# esquemacamiseta2.net
KiCad netlist of a schematic drawn in EAGLE
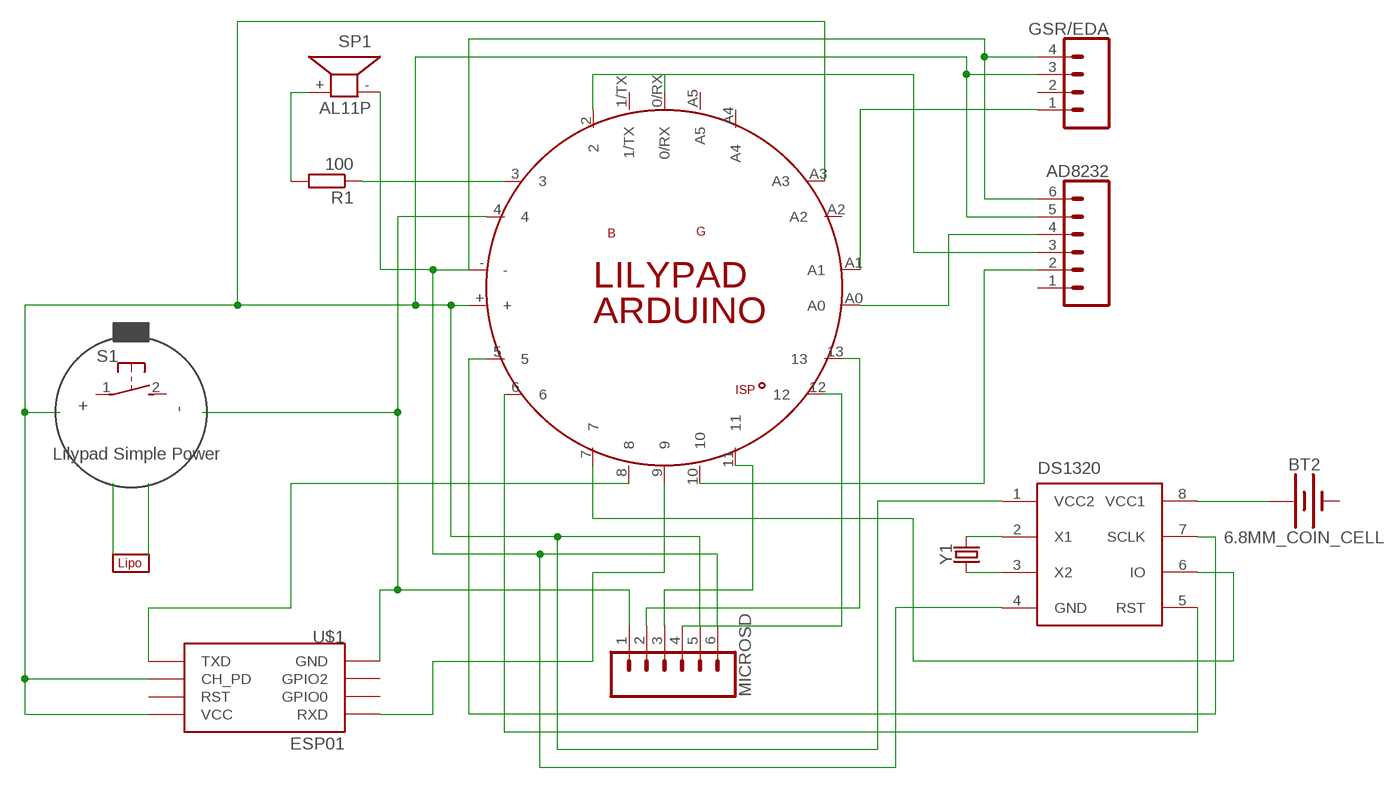
[diagram p0: schematic, sheet 1]

(export (version "E")
  (design (tool "Eeschema 10.0.6"))
  (components
    (comp (ref "AD8232")
      (value "CONN_06FEMALE_LOCK")
      (footprint "eagle-import:1X06_FEMALE_LOCK.010")
      (libsource (lib "eagle-import") (part "CONN_06FEMALE_LOCK"))
    )
    (comp (ref "BT1")
      (value "LIPO-OUTLINE1100")
      (footprint "eagle-import:LIPO-1000")
      (libsource (lib "eagle-import") (part "LIPO-OUTLINE1100"))
    )
    (comp (ref "BT2")
      (value "6.8MM_COIN_CELL")
      (footprint "eagle-import:BATTCON-6.8MM")
      (libsource (lib "eagle-import") (part "BATTERY-6.8MM_SMD"))
    )
    (comp (ref "DS1320")
      (value "DS1302")
      (footprint "eagle-import:PDIP8")
      (libsource (lib "eagle-import") (part "DS1302"))
    )
    (comp (ref "GSR/EDA")
      (value "CONN_04JST-PTH")
      (footprint "eagle-import:JST-4-PTH")
      (libsource (lib "eagle-import") (part "CONN_04JST-PTH"))
    )
    (comp (ref "MICROSD")
      (value "CONN_06FEMALE_LOCK")
      (footprint "eagle-import:1X06_FEMALE_LOCK.010")
      (libsource (lib "eagle-import") (part "CONN_06FEMALE_LOCK"))
    )
    (comp (ref "PCB1")
      (value "ARDUINO_LILYPAD")
      (footprint "eagle-import:ARDUINO_LILYPAD")
      (libsource (lib "eagle-import") (part "ARDUINO_LILYPAD"))
    )
    (comp (ref "R1")
      (value "100")
      (footprint "eagle-import:0309_12")
      (libsource (lib "eagle-import") (part "R-EU_0309/12"))
    )
    (comp (ref "S1")
      (value "31-XX")
      (footprint "eagle-import:B3F-31XX")
      (fields (field (name "MPN") "B3F-3100"))
      (libsource (lib "eagle-import") (part "31-XX"))
    )
    (comp (ref "SP1")
      (value "AL11P")
      (footprint "eagle-import:AL11P")
      (libsource (lib "eagle-import") (part "AL11P"))
    )
    (comp (ref "U$1")
      (value "ESP01")
      (footprint "eagle-import:ESP01")
      (libsource (lib "eagle-import") (part "ESP01"))
    )
    (comp (ref "Y1")
      (value "CRYSTALPTH-2X6")
      (footprint "eagle-import:CRYSTAL-PTH-2X6-CYL")
      (libsource (lib "eagle-import") (part "CRYSTALPTH-2X6"))
    )
  )
  (nets
    (net (code "1") (name "/-") (class "Default")
      (node (ref "BT2") (pin "-") (pinfunction "-_-") (pintype "power_in"))
    )
    (net (code "2") (name "Net-(AD8232-Pad2)") (class "Default")
      (node (ref "AD8232") (pin "2") (pinfunction "2_2") (pintype "passive"))
      (node (ref "PCB1") (pin "10") (pinfunction "10_10") (pintype "bidirectional"))
    )
    (net (code "3") (name "Net-(AD8232-Pad3)") (class "Default")
      (node (ref "AD8232") (pin "3") (pinfunction "3_3") (pintype "passive"))
      (node (ref "PCB1") (pin "2") (pinfunction "2_2") (pintype "bidirectional"))
    )
    (net (code "4") (name "Net-(AD8232-Pad4)") (class "Default")
      (node (ref "AD8232") (pin "4") (pinfunction "4_4") (pintype "passive"))
      (node (ref "PCB1") (pin "A0") (pinfunction "A0_A0") (pintype "bidirectional"))
    )
    (net (code "5") (name "Net-(DS1320-GND)") (class "Default")
      (node (ref "AD8232") (pin "6") (pinfunction "6_6") (pintype "passive"))
      (node (ref "DS1320") (pin "4") (pinfunction "GND_4") (pintype "power_in"))
      (node (ref "GSR/EDA") (pin "4") (pinfunction "4_4") (pintype "passive"))
      (node (ref "MICROSD") (pin "6") (pinfunction "6_6") (pintype "passive"))
      (node (ref "PCB1") (pin "-") (pinfunction "-_-") (pintype "bidirectional"))
      (node (ref "SP1") (pin "-") (pinfunction "1_-") (pintype "passive"))
    )
    (net (code "6") (name "Net-(DS1320-IO)") (class "Default")
      (node (ref "DS1320") (pin "6") (pinfunction "IO_6") (pintype "bidirectional"))
      (node (ref "PCB1") (pin "7") (pinfunction "7_7") (pintype "bidirectional"))
    )
    (net (code "7") (name "Net-(DS1320-RST)") (class "Default")
      (node (ref "DS1320") (pin "5") (pinfunction "RST_5") (pintype "input"))
      (node (ref "PCB1") (pin "6") (pinfunction "6_6") (pintype "bidirectional"))
    )
    (net (code "8") (name "Net-(DS1320-SCLK)") (class "Default")
      (node (ref "DS1320") (pin "7") (pinfunction "SCLK_7") (pintype "input"))
      (node (ref "PCB1") (pin "5") (pinfunction "5_5") (pintype "bidirectional"))
    )
    (net (code "9") (name "Net-(DS1320-VCC1)") (class "Default")
      (node (ref "BT2") (pin "+") (pinfunction "+_+") (pintype "power_in"))
      (node (ref "DS1320") (pin "8") (pinfunction "VCC1_8") (pintype "power_in"))
    )
    (net (code "10") (name "Net-(DS1320-VCC2)") (class "Default")
      (node (ref "AD8232") (pin "5") (pinfunction "5_5") (pintype "passive"))
      (node (ref "DS1320") (pin "1") (pinfunction "VCC2_1") (pintype "power_in"))
      (node (ref "GSR/EDA") (pin "3") (pinfunction "3_3") (pintype "passive"))
      (node (ref "MICROSD") (pin "5") (pinfunction "5_5") (pintype "passive"))
      (node (ref "PCB1") (pin "+") (pinfunction "+_+") (pintype "bidirectional"))
      (node (ref "PCB1") (pin "A3") (pinfunction "A3_A3") (pintype "bidirectional"))
      (node (ref "U$1") (pin "CH_PD") (pinfunction "CH_PD_CH_PD") (pintype "bidirectional"))
      (node (ref "U$1") (pin "VCC") (pinfunction "VCC_VCC") (pintype "bidirectional"))
    )
    (net (code "11") (name "Net-(DS1320-X1)") (class "Default")
      (node (ref "DS1320") (pin "2") (pinfunction "X1_2") (pintype "bidirectional"))
      (node (ref "Y1") (pin "2") (pinfunction "2_2") (pintype "passive"))
    )
    (net (code "12") (name "Net-(DS1320-X2)") (class "Default")
      (node (ref "DS1320") (pin "3") (pinfunction "X2_3") (pintype "bidirectional"))
      (node (ref "Y1") (pin "1") (pinfunction "1_1") (pintype "passive"))
    )
    (net (code "13") (name "Net-(GSR/EDA-Pad1)") (class "Default")
      (node (ref "GSR/EDA") (pin "1") (pinfunction "1_1") (pintype "passive"))
      (node (ref "PCB1") (pin "A1") (pinfunction "A1_A1") (pintype "bidirectional"))
    )
    (net (code "14") (name "Net-(MICROSD-Pad1)") (class "Default")
      (node (ref "MICROSD") (pin "1") (pinfunction "1_1") (pintype "passive"))
      (node (ref "PCB1") (pin "4") (pinfunction "4_4") (pintype "bidirectional"))
      (node (ref "U$1") (pin "GND") (pinfunction "GND_GND") (pintype "bidirectional"))
    )
    (net (code "15") (name "Net-(MICROSD-Pad2)") (class "Default")
      (node (ref "MICROSD") (pin "2") (pinfunction "2_2") (pintype "passive"))
      (node (ref "PCB1") (pin "13") (pinfunction "13_13") (pintype "bidirectional"))
    )
    (net (code "16") (name "Net-(MICROSD-Pad3)") (class "Default")
      (node (ref "MICROSD") (pin "3") (pinfunction "3_3") (pintype "passive"))
      (node (ref "PCB1") (pin "11") (pinfunction "11_11") (pintype "bidirectional"))
    )
    (net (code "17") (name "Net-(MICROSD-Pad4)") (class "Default")
      (node (ref "MICROSD") (pin "4") (pinfunction "4_4") (pintype "passive"))
      (node (ref "PCB1") (pin "12") (pinfunction "12_12") (pintype "bidirectional"))
    )
    (net (code "18") (name "Net-(PCB1-Pad3)") (class "Default")
      (node (ref "PCB1") (pin "3") (pinfunction "3_3") (pintype "bidirectional"))
      (node (ref "R1") (pin "1") (pinfunction "1_1") (pintype "passive"))
    )
    (net (code "19") (name "Net-(SP1-2)") (class "Default")
      (node (ref "R1") (pin "2") (pinfunction "2_2") (pintype "passive"))
      (node (ref "SP1") (pin "+") (pinfunction "2_+") (pintype "passive"))
    )
    (net (code "20") (name "Net-(U$1-RXD)") (class "Default")
      (node (ref "PCB1") (pin "9") (pinfunction "9_9") (pintype "bidirectional"))
      (node (ref "U$1") (pin "RX") (pinfunction "RXD_RX") (pintype "bidirectional"))
    )
    (net (code "21") (name "Net-(U$1-TXD)") (class "Default")
      (node (ref "PCB1") (pin "8") (pinfunction "8_8") (pintype "bidirectional"))
      (node (ref "U$1") (pin "TX") (pinfunction "TXD_TX") (pintype "bidirectional"))
    )
    (net (code "22") (name "unconnected-(AD8232-Pad1)") (class "Default")
      (node (ref "AD8232") (pin "1") (pinfunction "1_1") (pintype "passive"))
    )
    (net (code "23") (name "unconnected-(GSR/EDA-Pad2)") (class "Default")
      (node (ref "GSR/EDA") (pin "2") (pinfunction "2_2") (pintype "passive"))
    )
    (net (code "24") (name "unconnected-(PCB1-GND-PadGND_)") (class "Default")
      (node (ref "PCB1") (pin "GND_") (pinfunction "GND_GND_") (pintype "bidirectional"))
    )
    (net (code "25") (name "unconnected-(PCB1-Pad0{slash}RX)") (class "Default")
      (node (ref "PCB1") (pin "0/RX") (pinfunction "0/RX_0/RX") (pintype "bidirectional"))
    )
    (net (code "26") (name "unconnected-(PCB1-Pad1{slash}TX)") (class "Default")
      (node (ref "PCB1") (pin "1/TX") (pinfunction "1/TX_1/TX") (pintype "bidirectional"))
    )
    (net (code "27") (name "unconnected-(PCB1-PadA2)") (class "Default")
      (node (ref "PCB1") (pin "A2") (pinfunction "A2_A2") (pintype "bidirectional"))
    )
    (net (code "28") (name "unconnected-(PCB1-PadA4)") (class "Default")
      (node (ref "PCB1") (pin "A4") (pinfunction "A4_A4") (pintype "bidirectional"))
    )
    (net (code "29") (name "unconnected-(PCB1-PadA5)") (class "Default")
      (node (ref "PCB1") (pin "A5") (pinfunction "A5_A5") (pintype "bidirectional"))
    )
    (net (code "30") (name "unconnected-(PCB1-PadDTR)") (class "Default")
      (node (ref "PCB1") (pin "DTR") (pinfunction "DTR_DTR") (pintype "bidirectional"))
    )
    (net (code "31") (name "unconnected-(PCB1-PadGND.)") (class "Default")
      (node (ref "PCB1") (pin "GND.") (pinfunction "GND._GND.") (pintype "bidirectional"))
    )
    (net (code "32") (name "unconnected-(PCB1-PadGND..)") (class "Default")
      (node (ref "PCB1") (pin "GND..") (pinfunction "GND.._GND..") (pintype "bidirectional"))
    )
    (net (code "33") (name "unconnected-(PCB1-PadMISO)") (class "Default")
      (node (ref "PCB1") (pin "MISO") (pinfunction "MISO_MISO") (pintype "bidirectional"))
    )
    (net (code "34") (name "unconnected-(PCB1-PadMOSI)") (class "Default")
      (node (ref "PCB1") (pin "MOSI") (pinfunction "MOSI_MOSI") (pintype "bidirectional"))
    )
    (net (code "35") (name "unconnected-(PCB1-PadRXI)") (class "Default")
      (node (ref "PCB1") (pin "RXI") (pinfunction "RXI_RXI") (pintype "bidirectional"))
    )
    (net (code "36") (name "unconnected-(PCB1-PadSCK)") (class "Default")
      (node (ref "PCB1") (pin "SCK") (pinfunction "SCK_SCK") (pintype "bidirectional"))
    )
    (net (code "37") (name "unconnected-(PCB1-PadTXO)") (class "Default")
      (node (ref "PCB1") (pin "TXO") (pinfunction "TXO_TXO") (pintype "bidirectional"))
    )
    (net (code "38") (name "unconnected-(PCB1-PadVCC.)") (class "Default")
      (node (ref "PCB1") (pin "VCC.") (pinfunction "VCC._VCC.") (pintype "bidirectional"))
    )
    (net (code "39") (name "unconnected-(PCB1-RST-PadRESET..)") (class "Default")
      (node (ref "PCB1") (pin "RESET..") (pinfunction "RST_RESET..") (pintype "bidirectional"))
    )
    (net (code "40") (name "unconnected-(PCB1-VCC-Pad5V.)") (class "Default")
      (node (ref "PCB1") (pin "5V.") (pinfunction "VCC_5V.") (pintype "bidirectional"))
    )
    (net (code "41") (name "unconnected-(S1-P-Pad1)") (class "Default")
      (node (ref "S1") (pin "1") (pinfunction "P_1") (pintype "passive"))
    )
    (net (code "42") (name "unconnected-(S1-S-Pad2)") (class "Default")
      (node (ref "S1") (pin "2") (pinfunction "S_2") (pintype "passive"))
    )
    (net (code "43") (name "unconnected-(U$1-PadGPIO0)") (class "Default")
      (node (ref "U$1") (pin "GPIO0") (pinfunction "GPIO0_GPIO0") (pintype "bidirectional"))
    )
    (net (code "44") (name "unconnected-(U$1-PadGPIO2)") (class "Default")
      (node (ref "U$1") (pin "GPIO2") (pinfunction "GPIO2_GPIO2") (pintype "bidirectional"))
    )
    (net (code "45") (name "unconnected-(U$1-PadRST)") (class "Default")
      (node (ref "U$1") (pin "RST") (pinfunction "RST_RST") (pintype "bidirectional"))
    )
  )
)
